# Schematic.net
KiCad netlist of a schematic drawn in EAGLE
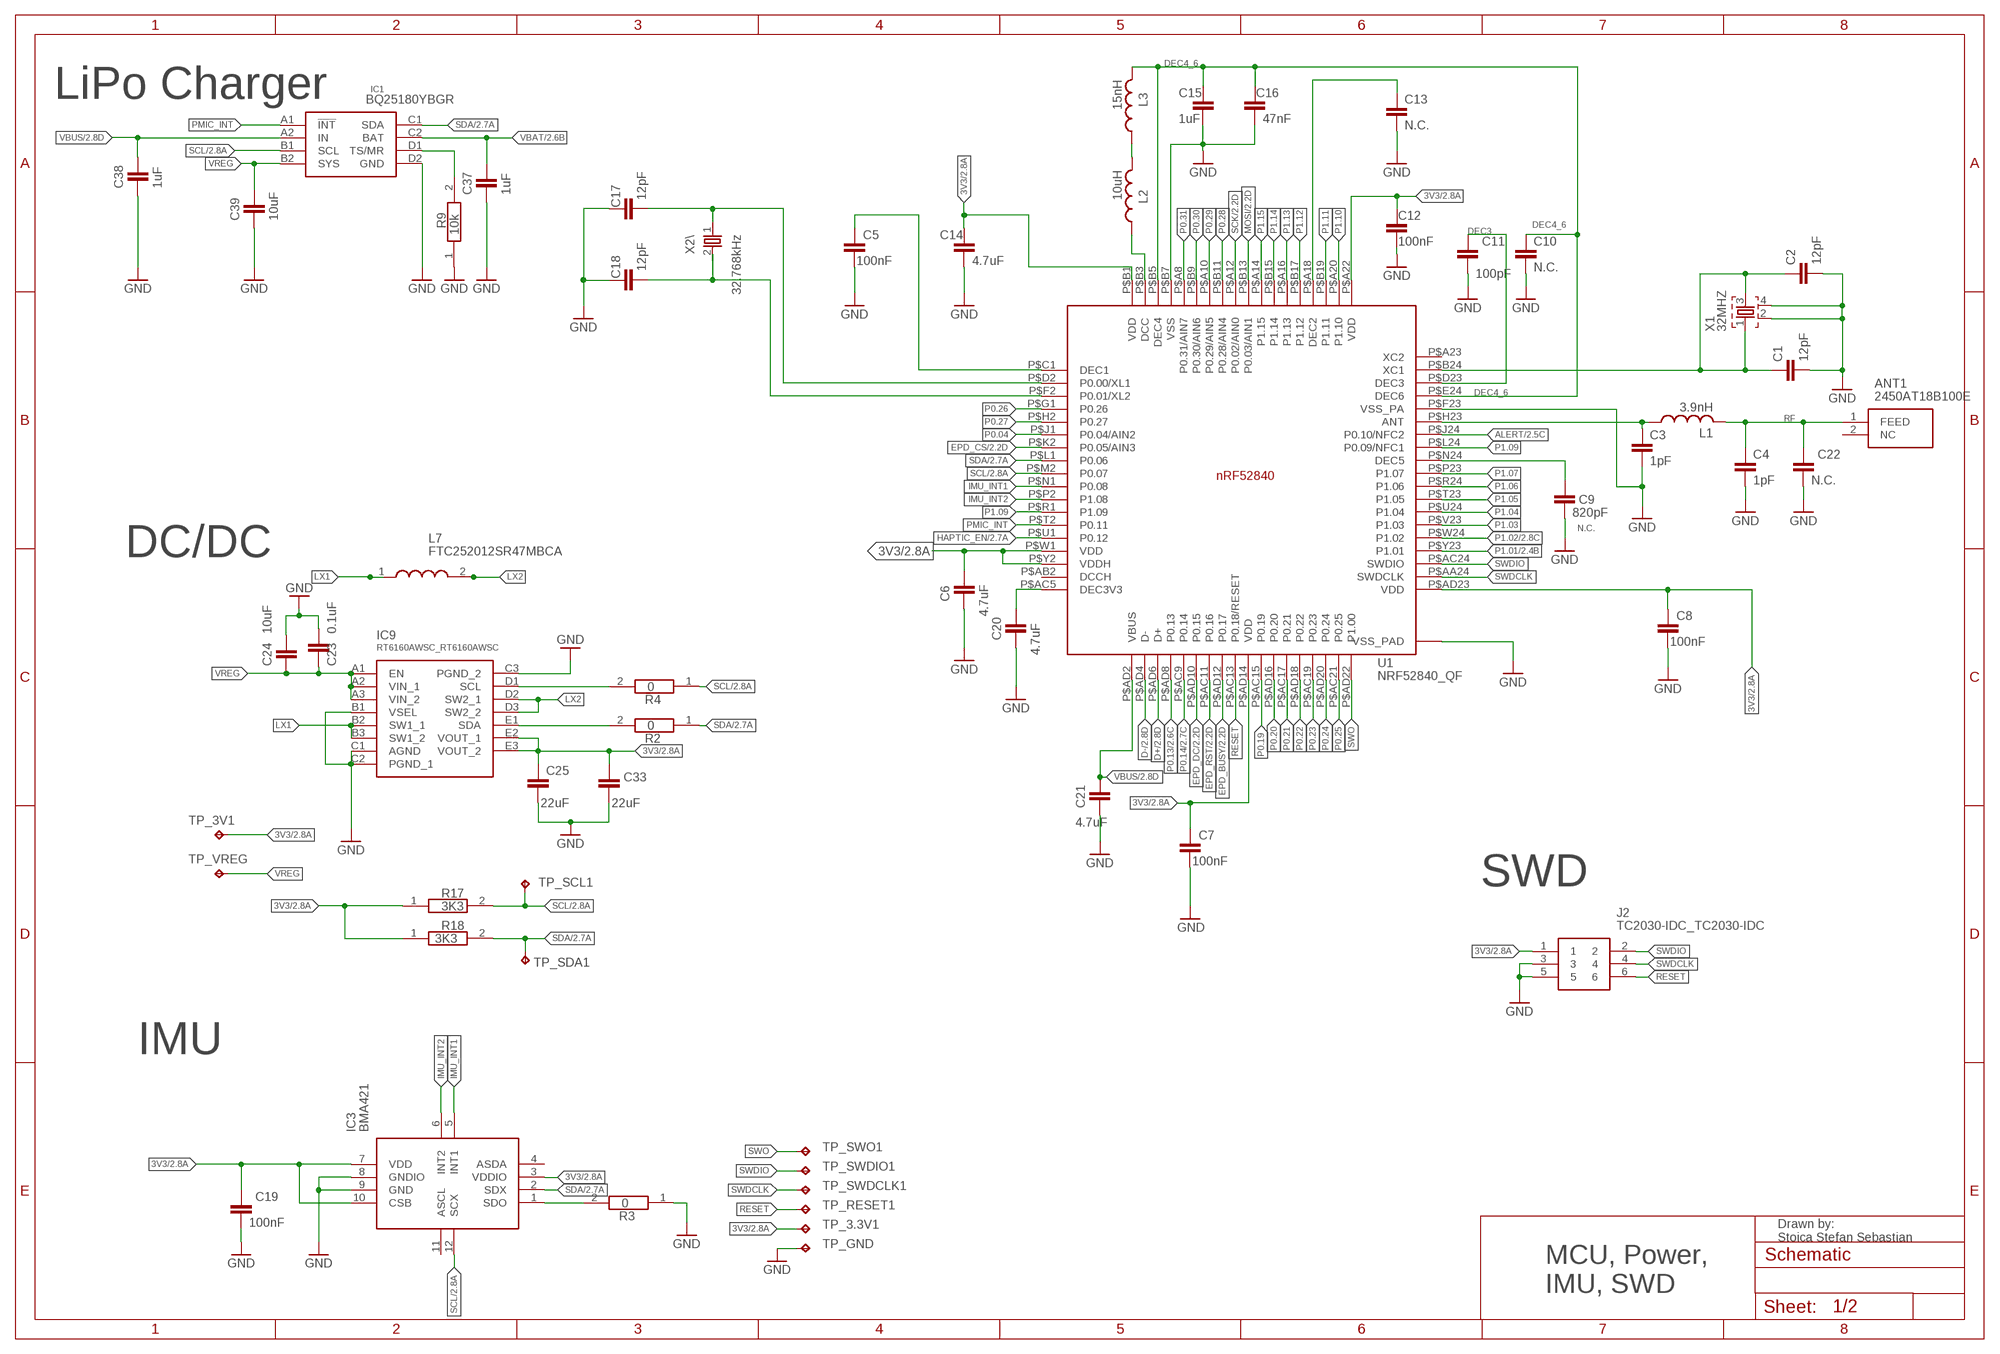
[diagram p0: schematic, sheet 1]
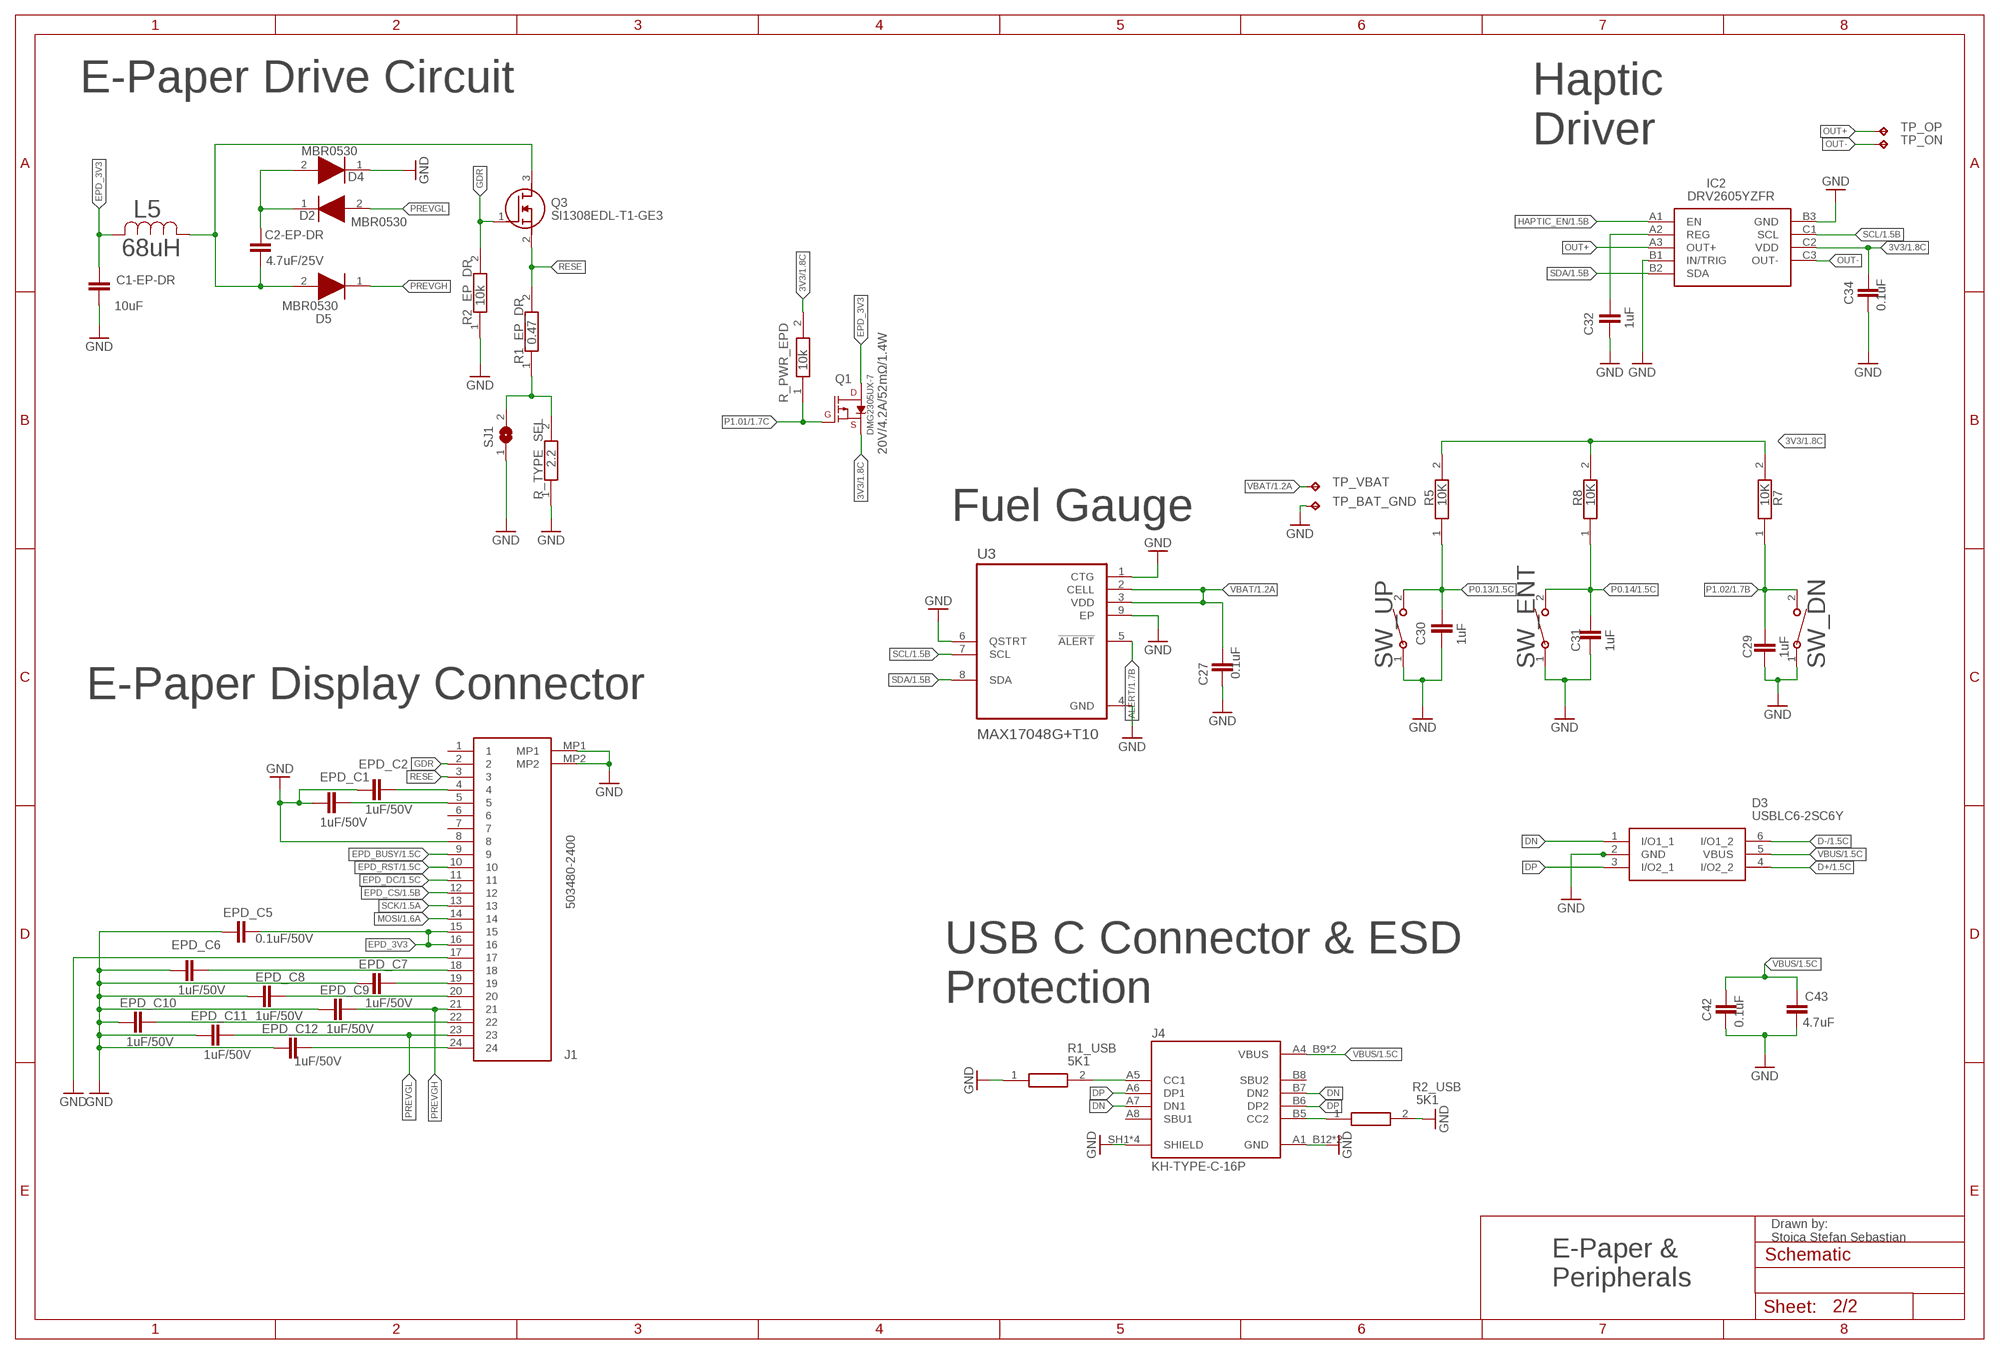
[diagram p1: schematic, sheet 2]

(export (version "E")
  (design (tool "Eeschema 10.0.6"))
  (components
    (comp (ref "C1-EP-DR")
      (value "10uF")
      (footprint "eagle-import:NORDIC_NRF_3_RESC0402_N")
      (libsource (lib "eagle-import") (part "NORDIC_NRF_3_CAPACITOR_0402_N"))
    )
    (comp (ref "C2-EP-DR")
      (value "4.7uF/25V")
      (footprint "eagle-import:NORDIC_NRF_3_RESC0603_N")
      (libsource (lib "eagle-import") (part "NORDIC_NRF_3_CAPACITOR_0603_N"))
    )
    (comp (ref "C27")
      (value "0.1uF")
      (footprint "eagle-import:NORDIC_NRF_3_RESC0201_N")
      (libsource (lib "eagle-import") (part "NORDIC_NRF_3_CAPACITOR_0201_N"))
    )
    (comp (ref "C29")
      (value "1uF")
      (footprint "eagle-import:NORDIC_NRF_3_RESC0402_N")
      (libsource (lib "eagle-import") (part "NORDIC_NRF_3_CAPACITOR_0402_N"))
    )
    (comp (ref "C30")
      (value "1uF")
      (footprint "eagle-import:NORDIC_NRF_3_RESC0402_N")
      (libsource (lib "eagle-import") (part "NORDIC_NRF_3_CAPACITOR_0402_N"))
    )
    (comp (ref "C31")
      (value "1uF")
      (footprint "eagle-import:NORDIC_NRF_3_RESC0402_N")
      (libsource (lib "eagle-import") (part "NORDIC_NRF_3_CAPACITOR_0402_N"))
    )
    (comp (ref "C32")
      (value "1uF")
      (footprint "eagle-import:NORDIC_NRF_3_RESC0402_N")
      (libsource (lib "eagle-import") (part "NORDIC_NRF_3_CAPACITOR_0402_N"))
    )
    (comp (ref "C34")
      (value "0.1uF")
      (footprint "eagle-import:NORDIC_NRF_3_RESC0201_N")
      (libsource (lib "eagle-import") (part "NORDIC_NRF_3_CAPACITOR_0201_N"))
    )
    (comp (ref "C42")
      (value "0.1uF")
      (footprint "eagle-import:NORDIC_NRF_3_RESC0201_N")
      (libsource (lib "eagle-import") (part "NORDIC_NRF_3_CAPACITOR_0201_N"))
    )
    (comp (ref "C43")
      (value "4.7uF")
      (footprint "eagle-import:NORDIC_NRF_3_RESC0402_N")
      (libsource (lib "eagle-import") (part "NORDIC_NRF_3_CAPACITOR_0402_N"))
    )
    (comp (ref "D2")
      (value "MBR0530")
      (footprint "eagle-import:ESP32_C6_LIBRARY_5_SOD3716X135N")
      (fields (field (name "MF") "ON Semiconductor"))
      (libsource (lib "eagle-import") (part "ESP32_C6_LIBRARY_5_MBR0530"))
    )
    (comp (ref "D3")
      (value "USBLC6-2SC6Y")
      (footprint "eagle-import:ESP32_C6_LIBRARY_3_SOT95P280X145-6N")
      (fields (field (name "MF") "STMicroelectronics"))
      (libsource (lib "eagle-import") (part "ESP32_C6_LIBRARY_3_USBLC6-2SC6Y"))
    )
    (comp (ref "D4")
      (value "MBR0530")
      (footprint "eagle-import:ESP32_C6_LIBRARY_5_SOD3716X135N")
      (fields (field (name "MF") "ON Semiconductor"))
      (libsource (lib "eagle-import") (part "ESP32_C6_LIBRARY_5_MBR0530"))
    )
    (comp (ref "D5")
      (value "MBR0530")
      (footprint "eagle-import:ESP32_C6_LIBRARY_5_SOD3716X135N")
      (fields (field (name "MF") "ON Semiconductor"))
      (libsource (lib "eagle-import") (part "ESP32_C6_LIBRARY_5_MBR0530"))
    )
    (comp (ref "EPD_C1")
      (value "1uF/50V")
      (footprint "eagle-import:NORDIC_NRF_3_RESC0402_N")
      (libsource (lib "eagle-import") (part "NORDIC_NRF_3_CAPACITOR_0402_N"))
    )
    (comp (ref "EPD_C2")
      (value "1uF/50V")
      (footprint "eagle-import:NORDIC_NRF_3_RESC0402_N")
      (libsource (lib "eagle-import") (part "NORDIC_NRF_3_CAPACITOR_0402_N"))
    )
    (comp (ref "EPD_C5")
      (value "0.1uF/50V")
      (footprint "eagle-import:NORDIC_NRF_3_RESC0402_N")
      (libsource (lib "eagle-import") (part "NORDIC_NRF_3_CAPACITOR_0402_N"))
    )
    (comp (ref "EPD_C6")
      (value "1uF/50V")
      (footprint "eagle-import:NORDIC_NRF_3_RESC0402_N")
      (libsource (lib "eagle-import") (part "NORDIC_NRF_3_CAPACITOR_0402_N"))
    )
    (comp (ref "EPD_C7")
      (value "1uF/50V")
      (footprint "eagle-import:NORDIC_NRF_3_RESC0402_N")
      (libsource (lib "eagle-import") (part "NORDIC_NRF_3_CAPACITOR_0402_N"))
    )
    (comp (ref "EPD_C8")
      (value "1uF/50V")
      (footprint "eagle-import:NORDIC_NRF_3_RESC0402_N")
      (libsource (lib "eagle-import") (part "NORDIC_NRF_3_CAPACITOR_0402_N"))
    )
    (comp (ref "EPD_C9")
      (value "1uF/50V")
      (footprint "eagle-import:NORDIC_NRF_3_RESC0402_N")
      (libsource (lib "eagle-import") (part "NORDIC_NRF_3_CAPACITOR_0402_N"))
    )
    (comp (ref "EPD_C10")
      (value "1uF/50V")
      (footprint "eagle-import:NORDIC_NRF_3_RESC0402_N")
      (libsource (lib "eagle-import") (part "NORDIC_NRF_3_CAPACITOR_0402_N"))
    )
    (comp (ref "EPD_C11")
      (value "1uF/50V")
      (footprint "eagle-import:NORDIC_NRF_3_RESC0402_N")
      (libsource (lib "eagle-import") (part "NORDIC_NRF_3_CAPACITOR_0402_N"))
    )
    (comp (ref "EPD_C12")
      (value "1uF/50V")
      (footprint "eagle-import:NORDIC_NRF_3_RESC0402_N")
      (libsource (lib "eagle-import") (part "NORDIC_NRF_3_CAPACITOR_0402_N"))
    )
    (comp (ref "IC2")
      (value "DRV2605YZFR")
      (footprint "eagle-import:DRV2605YZFR_BGA9C50P3X3_144X144X62")
      (libsource (lib "eagle-import") (part "DRV2605YZFR_DRV2605YZFR"))
    )
    (comp (ref "J1")
      (value "503480-2400")
      (footprint "eagle-import:503480-2400_5034802400")
      (fields (field (name "MOUSER_PART_NUMBER") "538-503480-2400"))
      (libsource (lib "eagle-import") (part "503480-2400_503480-2400"))
    )
    (comp (ref "J4")
      (value "KH-TYPE-C-16P")
      (footprint "eagle-import:KH-TYPE-C-16P_KINGHELM_KH-TYPE-C-16P")
      (fields (field (name "MF") "kinghelm"))
      (libsource (lib "eagle-import") (part "KH-TYPE-C-16P_KH-TYPE-C-16P"))
    )
    (comp (ref "L5")
      (value "68uH")
      (footprint "eagle-import:ESP32_C6_LIBRARY_2_IND_4828-WE-TPC_WRE")
      (fields
        (field (name "MANUFACTURER_PART_NUMBER") "744043680")
        (field (name "COPYRIGHT") "Copyright (C) 2024 Ultra Librarian. All rights reserved.")
      )
      (libsource (lib "eagle-import") (part "ESP32_C6_LIBRARY_2_744043680IND_4828-WE-TPC_WRE"))
    )
    (comp (ref "Q1")
      (value "20V/4.2A/52mΩ/1.4W")
      (footprint "eagle-import:ESP32_C6_LIBRARY_4_ESP32_C6_LIBRARY_4_ESP32_C6_LIBRARY_4_ESP32_C6_LIBRARY_4_ESP32_WROVER_SPARKFUN-DISCRETESEMI_SOT23-3")
      (libsource (lib "eagle-import") (part "ESP32_C6_LIBRARY_4_ESP32_WROVER_SPARKFUN-DISCRETESEMI_MOSFET_PCH-DMG2305UX-7"))
    )
    (comp (ref "Q3")
      (value "SI1308EDL-T1-GE3")
      (footprint "eagle-import:ESP32_C6_LIBRARY_6_SOT65P210X110-3N")
      (fields (field (name "MF") "Vishay Siliconix"))
      (libsource (lib "eagle-import") (part "ESP32_C6_LIBRARY_6_SI1308EDL-T1-GE3"))
    )
    (comp (ref "R1_EP_DR")
      (value "0.47")
      (footprint "eagle-import:CPF0201D7K68C1_0201")
      (libsource (lib "eagle-import") (part "CPF0201D7K68C1_CPF0201D7K68C1"))
    )
    (comp (ref "R1_USB")
      (value "5K1")
      (footprint "eagle-import:CPF0201D7K68C1_0201")
      (libsource (lib "eagle-import") (part "CPF0201D7K68C1_CPF0201D7K68C1"))
    )
    (comp (ref "R2_EP_DR")
      (value "10k")
      (footprint "eagle-import:CPF0201D7K68C1_0201")
      (libsource (lib "eagle-import") (part "CPF0201D7K68C1_CPF0201D7K68C1"))
    )
    (comp (ref "R2_USB")
      (value "5K1")
      (footprint "eagle-import:CPF0201D7K68C1_0201")
      (libsource (lib "eagle-import") (part "CPF0201D7K68C1_CPF0201D7K68C1"))
    )
    (comp (ref "R5")
      (value "10K")
      (footprint "eagle-import:CPF0201D7K68C1_0201")
      (libsource (lib "eagle-import") (part "CPF0201D7K68C1_CPF0201D7K68C1"))
    )
    (comp (ref "R7")
      (value "10K")
      (footprint "eagle-import:CPF0201D7K68C1_0201")
      (libsource (lib "eagle-import") (part "CPF0201D7K68C1_CPF0201D7K68C1"))
    )
    (comp (ref "R8")
      (value "10K")
      (footprint "eagle-import:CPF0201D7K68C1_0201")
      (libsource (lib "eagle-import") (part "CPF0201D7K68C1_CPF0201D7K68C1"))
    )
    (comp (ref "R_PWR_EPD")
      (value "10k")
      (footprint "eagle-import:CPF0201D7K68C1_0201")
      (libsource (lib "eagle-import") (part "CPF0201D7K68C1_CPF0201D7K68C1"))
    )
    (comp (ref "R_TYPE_SEL")
      (value "2.2")
      (footprint "eagle-import:CPF0201D7K68C1_0201")
      (libsource (lib "eagle-import") (part "CPF0201D7K68C1_CPF0201D7K68C1"))
    )
    (comp (ref "SJ1")
      (value "ESP32_C6_LIBRARY_7_JUMPER_SJ")
      (footprint "eagle-import:ESP32_C6_LIBRARY_7_JUMPER_SJ")
      (libsource (lib "eagle-import") (part "ESP32_C6_LIBRARY_7_JUMPER_SJ"))
    )
    (comp (ref "SW_DN")
      (value "2025-10-22_07-23-44_LIBRARY_EVP-AKE31ASW_EVP-AKE31A_PAN")
      (footprint "eagle-import:2025-10-22_07-23-44_LIBRARY_SW_EVP-AKE31A_PAN")
      (fields
        (field (name "MANUFACTURER_PART_NUMBER") "EVP-AKE31A")
        (field (name "COPYRIGHT") "Copyright (C) 2025 Ultra Librarian. All rights reserved.")
      )
      (libsource (lib "eagle-import") (part "2025-10-22_07-23-44_LIBRARY_EVP-AKE31ASW_EVP-AKE31A_PAN"))
    )
    (comp (ref "SW_ENT")
      (value "2025-10-22_07-23-44_LIBRARY_EVP-AKE31ASW_EVP-AKE31A_PAN")
      (footprint "eagle-import:2025-10-22_07-23-44_LIBRARY_SW_EVP-AKE31A_PAN")
      (fields
        (field (name "MANUFACTURER_PART_NUMBER") "EVP-AKE31A")
        (field (name "COPYRIGHT") "Copyright (C) 2025 Ultra Librarian. All rights reserved.")
      )
      (libsource (lib "eagle-import") (part "2025-10-22_07-23-44_LIBRARY_EVP-AKE31ASW_EVP-AKE31A_PAN"))
    )
    (comp (ref "SW_UP")
      (value "2025-10-22_07-23-44_LIBRARY_EVP-AKE31ASW_EVP-AKE31A_PAN")
      (footprint "eagle-import:2025-10-22_07-23-44_LIBRARY_SW_EVP-AKE31A_PAN")
      (fields
        (field (name "MANUFACTURER_PART_NUMBER") "EVP-AKE31A")
        (field (name "COPYRIGHT") "Copyright (C) 2025 Ultra Librarian. All rights reserved.")
      )
      (libsource (lib "eagle-import") (part "2025-10-22_07-23-44_LIBRARY_EVP-AKE31ASW_EVP-AKE31A_PAN"))
    )
    (comp (ref "TP_BAT_GND")
      (value "HECTOR_WATCH_1_TPTP20R")
      (footprint "eagle-import:HECTOR_WATCH_1_TP20R")
      (libsource (lib "eagle-import") (part "HECTOR_WATCH_1_TPTP20R"))
    )
    (comp (ref "TP_ON")
      (value "HECTOR_WATCH_1_TPTP20R")
      (footprint "eagle-import:HECTOR_WATCH_1_TP20R")
      (libsource (lib "eagle-import") (part "HECTOR_WATCH_1_TPTP20R"))
    )
    (comp (ref "TP_OP")
      (value "HECTOR_WATCH_1_TPTP20R")
      (footprint "eagle-import:HECTOR_WATCH_1_TP20R")
      (libsource (lib "eagle-import") (part "HECTOR_WATCH_1_TPTP20R"))
    )
    (comp (ref "TP_VBAT")
      (value "HECTOR_WATCH_1_TPTP20R")
      (footprint "eagle-import:HECTOR_WATCH_1_TP20R")
      (libsource (lib "eagle-import") (part "HECTOR_WATCH_1_TPTP20R"))
    )
    (comp (ref "U3")
      (value "MAX17048G+T10")
      (footprint "eagle-import:ESP32_C6_LIBRARY_SON50P200X200X80-9N")
      (fields (field (name "MF") "Analog Devices"))
      (libsource (lib "eagle-import") (part "ESP32_C6_LIBRARY_MAX17048G+T10"))
    )
    (comp (ref "ANT1")
      (value "2450AT18B100E")
      (footprint "eagle-import:2450AT18B100E_ANTC3216X140N")
      (fields (field (name "MOUSER_PART_NUMBER") "609-2450AT18B100E"))
      (libsource (lib "eagle-import") (part "2450AT18B100E_2450AT18B100E"))
    )
    (comp (ref "C1")
      (value "12pF")
      (footprint "eagle-import:NORDIC_NRF_3_RESC0201_N")
      (libsource (lib "eagle-import") (part "NORDIC_NRF_3_CAPACITOR_0201_N"))
    )
    (comp (ref "C2")
      (value "12pF")
      (footprint "eagle-import:NORDIC_NRF_3_RESC0201_N")
      (libsource (lib "eagle-import") (part "NORDIC_NRF_3_CAPACITOR_0201_N"))
    )
    (comp (ref "C3")
      (value "1pF")
      (footprint "eagle-import:NORDIC_NRF_3_RESC0201_N")
      (libsource (lib "eagle-import") (part "NORDIC_NRF_3_CAPACITOR_0201_N"))
    )
    (comp (ref "C4")
      (value "1pF")
      (footprint "eagle-import:NORDIC_NRF_3_RESC0201_N")
      (libsource (lib "eagle-import") (part "NORDIC_NRF_3_CAPACITOR_0201_N"))
    )
    (comp (ref "C5")
      (value "100nF")
      (footprint "eagle-import:NORDIC_NRF_3_RESC0201_N")
      (libsource (lib "eagle-import") (part "NORDIC_NRF_3_CAPACITOR_0201_N"))
    )
    (comp (ref "C6")
      (value "4.7uF")
      (footprint "eagle-import:NORDIC_NRF_3_RESC0402_N")
      (libsource (lib "eagle-import") (part "NORDIC_NRF_3_CAPACITOR_0402_N"))
    )
    (comp (ref "C7")
      (value "100nF")
      (footprint "eagle-import:NORDIC_NRF_3_RESC0201_N")
      (libsource (lib "eagle-import") (part "NORDIC_NRF_3_CAPACITOR_0201_N"))
    )
    (comp (ref "C8")
      (value "100nF")
      (footprint "eagle-import:NORDIC_NRF_3_RESC0201_N")
      (libsource (lib "eagle-import") (part "NORDIC_NRF_3_CAPACITOR_0201_N"))
    )
    (comp (ref "C9")
      (value "820pF")
      (footprint "eagle-import:NORDIC_NRF_3_RESC0201_N")
      (libsource (lib "eagle-import") (part "NORDIC_NRF_3_CAPACITOR_0201_N"))
    )
    (comp (ref "C10")
      (value "N.C.")
      (footprint "eagle-import:NORDIC_NRF_3_RESC0201_N")
      (libsource (lib "eagle-import") (part "NORDIC_NRF_3_CAPACITOR_0201_N"))
    )
    (comp (ref "C11")
      (value "100pF")
      (footprint "eagle-import:NORDIC_NRF_3_RESC0201_N")
      (libsource (lib "eagle-import") (part "NORDIC_NRF_3_CAPACITOR_0201_N"))
    )
    (comp (ref "C12")
      (value "100nF")
      (footprint "eagle-import:NORDIC_NRF_3_RESC0201_N")
      (libsource (lib "eagle-import") (part "NORDIC_NRF_3_CAPACITOR_0201_N"))
    )
    (comp (ref "C13")
      (value "N.C.")
      (footprint "eagle-import:NORDIC_NRF_3_RESC0201_N")
      (libsource (lib "eagle-import") (part "NORDIC_NRF_3_CAPACITOR_0201_N"))
    )
    (comp (ref "C14")
      (value "4.7uF")
      (footprint "eagle-import:NORDIC_NRF_3_RESC0402_N")
      (libsource (lib "eagle-import") (part "NORDIC_NRF_3_CAPACITOR_0402_N"))
    )
    (comp (ref "C15")
      (value "1uF")
      (footprint "eagle-import:NORDIC_NRF_3_RESC0402_N")
      (libsource (lib "eagle-import") (part "NORDIC_NRF_3_CAPACITOR_0402_N"))
    )
    (comp (ref "C16")
      (value "47nF")
      (footprint "eagle-import:NORDIC_NRF_3_RESC0201_N")
      (libsource (lib "eagle-import") (part "NORDIC_NRF_3_CAPACITOR_0201_N"))
    )
    (comp (ref "C17")
      (value "12pF")
      (footprint "eagle-import:NORDIC_NRF_3_RESC0201_N")
      (libsource (lib "eagle-import") (part "NORDIC_NRF_3_CAPACITOR_0201_N"))
    )
    (comp (ref "C18")
      (value "12pF")
      (footprint "eagle-import:NORDIC_NRF_3_RESC0201_N")
      (libsource (lib "eagle-import") (part "NORDIC_NRF_3_CAPACITOR_0201_N"))
    )
    (comp (ref "C19")
      (value "100nF")
      (footprint "eagle-import:NORDIC_NRF_3_RESC0201_N")
      (libsource (lib "eagle-import") (part "NORDIC_NRF_3_CAPACITOR_0201_N"))
    )
    (comp (ref "C20")
      (value "4.7uF")
      (footprint "eagle-import:NORDIC_NRF_3_RESC0402_N")
      (libsource (lib "eagle-import") (part "NORDIC_NRF_3_CAPACITOR_0402_N"))
    )
    (comp (ref "C21")
      (value "4.7uF")
      (footprint "eagle-import:NORDIC_NRF_3_RESC0402_N")
      (libsource (lib "eagle-import") (part "NORDIC_NRF_3_CAPACITOR_0402_N"))
    )
    (comp (ref "C22")
      (value "N.C.")
      (footprint "eagle-import:NORDIC_NRF_3_RESC0201_N")
      (libsource (lib "eagle-import") (part "NORDIC_NRF_3_CAPACITOR_0201_N"))
    )
    (comp (ref "C23")
      (value "0.1uF")
      (footprint "eagle-import:NORDIC_NRF_3_RESC0201_N")
      (libsource (lib "eagle-import") (part "NORDIC_NRF_3_CAPACITOR_0201_N"))
    )
    (comp (ref "C24")
      (value "10uF")
      (footprint "eagle-import:NORDIC_NRF_3_RESC0402_N")
      (libsource (lib "eagle-import") (part "NORDIC_NRF_3_CAPACITOR_0402_N"))
    )
    (comp (ref "C25")
      (value "22uF")
      (footprint "eagle-import:NORDIC_NRF_3_RESC0603_N")
      (libsource (lib "eagle-import") (part "InkTime_v5_vf.birtyhFxSUisHCd2wUyXPg_NORDIC_NRF_3_CAPACITOR_0603_N"))
    )
    (comp (ref "C33")
      (value "22uF")
      (footprint "eagle-import:NORDIC_NRF_3_RESC0603_N")
      (libsource (lib "eagle-import") (part "InkTime_v5_vf.birtyhFxSUisHCd2wUyXPg_NORDIC_NRF_3_CAPACITOR_0603_N"))
    )
    (comp (ref "C37")
      (value "1uF")
      (footprint "eagle-import:NORDIC_NRF_3_RESC0402_N")
      (libsource (lib "eagle-import") (part "NORDIC_NRF_3_CAPACITOR_0402_N"))
    )
    (comp (ref "C38")
      (value "1uF")
      (footprint "eagle-import:NORDIC_NRF_3_RESC0402_N")
      (libsource (lib "eagle-import") (part "NORDIC_NRF_3_CAPACITOR_0402_N"))
    )
    (comp (ref "C39")
      (value "10uF")
      (footprint "eagle-import:NORDIC_NRF_3_RESC0603_N")
      (libsource (lib "eagle-import") (part "InkTime_v5_vf.birtyhFxSUisHCd2wUyXPg_NORDIC_NRF_3_CAPACITOR_0603_N"))
    )
    (comp (ref "IC1")
      (value "BQ25180YBGR")
      (footprint "eagle-import:BQ25180YBGR_BGA8C40P2X4_100X155X50")
      (fields (field (name "MOUSER_PART_NUMBER") "595-BQ25180YBGR"))
      (libsource (lib "eagle-import") (part "BQ25180YBGR_BQ25180YBGR"))
    )
    (comp (ref "IC3")
      (value "BMA421")
      (footprint "eagle-import:BMA423_BMA423")
      (fields
        (field (name "ARROW_PART_NUMBER") "BMA423")
        (field (name "MOUSER_PART_NUMBER") "262-BMA423")
        (field (name "ARROW_PART_NUMBER_1") "BMA421")
        (field (name "MANUFACTURER_PART_NUMBER") "BMA421")
        (field (name "MOUSER_PART_NUMBER_1") "262-BMA421")
      )
      (libsource (lib "eagle-import") (part "BMA423_BMA423"))
    )
    (comp (ref "IC9")
      (value "RT6160AWSC_RT6160AWSC")
      (footprint "eagle-import:RT6160AWSC_BGA15C40P3X5_140X230X60")
      (fields
        (field (name "MANUFACTURER_PART_NUMBER") "RT6160AWSC")
        (field (name "MOUSER_PART_NUMBER") "835-RT6160AWSC")
      )
      (libsource (lib "eagle-import") (part "RT6160AWSC_RT6160AWSC"))
    )
    (comp (ref "J2")
      (value "TC2030-IDC_TC2030-IDC")
      (footprint "eagle-import:TC2030-IDC_TC2030IDC")
      (fields (field (name "MANUFACTURER_PART_NUMBER") "TC2030-IDC"))
      (libsource (lib "eagle-import") (part "TC2030-IDC_TC2030-IDC"))
    )
    (comp (ref "L1")
      (value "3.9nH")
      (footprint "eagle-import:NORDIC_NRF_2_RESC0402_L")
      (libsource (lib "eagle-import") (part "NORDIC_NRF_2_INDUCTOR_0402_L"))
    )
    (comp (ref "L2")
      (value "10uH")
      (footprint "eagle-import:NORDIC_NRF_2_RESC0603_N")
      (libsource (lib "eagle-import") (part "InkTime_v5_vf.birtyhFxSUisHCd2wUyXPg_NORDIC_NRF_2_INDUCTOR_0603_N"))
    )
    (comp (ref "L3")
      (value "15nH")
      (footprint "eagle-import:NORDIC_NRF_2_RESC0402_L")
      (libsource (lib "eagle-import") (part "NORDIC_NRF_2_INDUCTOR_0402_L"))
    )
    (comp (ref "L7")
      (value "FTC252012SR47MBCA")
      (footprint "eagle-import:MLP2016SR47MT0S1_INDC2016X100N")
      (libsource (lib "eagle-import") (part "MLP2016SR47MT0S1_FTC252012SR47MBCA"))
    )
    (comp (ref "R2")
      (value "0")
      (footprint "eagle-import:CPF0201D7K68C1_0201")
      (libsource (lib "eagle-import") (part "CPF0201D7K68C1_CPF0201D7K68C1"))
    )
    (comp (ref "R3")
      (value "0")
      (footprint "eagle-import:CPF0201D7K68C1_0201")
      (libsource (lib "eagle-import") (part "CPF0201D7K68C1_CPF0201D7K68C1"))
    )
    (comp (ref "R4")
      (value "0")
      (footprint "eagle-import:CPF0201D7K68C1_0201")
      (libsource (lib "eagle-import") (part "CPF0201D7K68C1_CPF0201D7K68C1"))
    )
    (comp (ref "R9")
      (value "10k")
      (footprint "eagle-import:CPF0201D7K68C1_0201")
      (libsource (lib "eagle-import") (part "CPF0201D7K68C1_CPF0201D7K68C1"))
    )
    (comp (ref "R17")
      (value "3K3")
      (footprint "eagle-import:CPF0201D7K68C1_0201")
      (libsource (lib "eagle-import") (part "CPF0201D7K68C1_CPF0201D7K68C1"))
    )
    (comp (ref "R18")
      (value "3K3")
      (footprint "eagle-import:CPF0201D7K68C1_0201")
      (libsource (lib "eagle-import") (part "CPF0201D7K68C1_CPF0201D7K68C1"))
    )
    (comp (ref "TP_3.3V1")
      (value "HECTOR_WATCH_1_TPTP20R")
      (footprint "eagle-import:HECTOR_WATCH_1_TP20R")
      (libsource (lib "eagle-import") (part "HECTOR_WATCH_1_TPTP20R"))
    )
    (comp (ref "TP_3V1")
      (value "HECTOR_WATCH_1_TPTP20R")
      (footprint "eagle-import:HECTOR_WATCH_1_TP20R")
      (libsource (lib "eagle-import") (part "HECTOR_WATCH_1_TPTP20R"))
    )
    (comp (ref "TP_GND")
      (value "HECTOR_WATCH_1_TPTP20R")
      (footprint "eagle-import:HECTOR_WATCH_1_TP20R")
      (libsource (lib "eagle-import") (part "HECTOR_WATCH_1_TPTP20R"))
    )
    (comp (ref "TP_RESET1")
      (value "HECTOR_WATCH_1_TPTP20R")
      (footprint "eagle-import:HECTOR_WATCH_1_TP20R")
      (libsource (lib "eagle-import") (part "HECTOR_WATCH_1_TPTP20R"))
    )
    (comp (ref "TP_SCL1")
      (value "HECTOR_WATCH_1_TPTP20R")
      (footprint "eagle-import:HECTOR_WATCH_1_TP20R")
      (libsource (lib "eagle-import") (part "HECTOR_WATCH_1_TPTP20R"))
    )
    (comp (ref "TP_SDA1")
      (value "HECTOR_WATCH_1_TPTP20R")
      (footprint "eagle-import:HECTOR_WATCH_1_TP20R")
      (libsource (lib "eagle-import") (part "HECTOR_WATCH_1_TPTP20R"))
    )
    (comp (ref "TP_SWDCLK1")
      (value "HECTOR_WATCH_1_TPTP20R")
      (footprint "eagle-import:HECTOR_WATCH_1_TP20R")
      (libsource (lib "eagle-import") (part "HECTOR_WATCH_1_TPTP20R"))
    )
    (comp (ref "TP_SWDIO1")
      (value "HECTOR_WATCH_1_TPTP20R")
      (footprint "eagle-import:HECTOR_WATCH_1_TP20R")
      (libsource (lib "eagle-import") (part "HECTOR_WATCH_1_TPTP20R"))
    )
    (comp (ref "TP_SWO1")
      (value "HECTOR_WATCH_1_TPTP20R")
      (footprint "eagle-import:HECTOR_WATCH_1_TP20R")
      (libsource (lib "eagle-import") (part "HECTOR_WATCH_1_TPTP20R"))
    )
    (comp (ref "TP_VREG")
      (value "HECTOR_WATCH_1_TPTP20R")
      (footprint "eagle-import:HECTOR_WATCH_1_TP20R")
      (libsource (lib "eagle-import") (part "HECTOR_WATCH_1_TPTP20R"))
    )
    (comp (ref "U1")
      (value "NRF52840_QF")
      (footprint "eagle-import:NORDIC_NRF_4_AQFN50P700X700X85_HS-74N")
      (libsource (lib "eagle-import") (part "NORDIC_NRF_4_NRF52840_QF"))
    )
    (comp (ref "X1")
      (value "32MHZ")
      (footprint "eagle-import:NORDIC_NRF_BT-XTAL_2016_N")
      (libsource (lib "eagle-import") (part "NORDIC_NRF_XTAL_32MHZ"))
    )
    (comp (ref "X2\\")
      (value "32.768kHz")
      (footprint "eagle-import:NORDIC_NRF_1_XTAL_3215_N")
      (libsource (lib "eagle-import") (part "NORDIC_NRF_1_XTAL_32KHZ"))
    )
  )
  (nets
    (net (code "1") (name "3V3") (class "Default")
      (node (ref "C12") (pin "2") (pinfunction "2_2") (pintype "passive"))
      (node (ref "C14") (pin "1") (pinfunction "1_1") (pintype "passive"))
      (node (ref "C19") (pin "2") (pinfunction "2_2") (pintype "passive"))
      (node (ref "C25") (pin "1") (pinfunction "1_1") (pintype "passive"))
      (node (ref "C33") (pin "1") (pinfunction "1_1") (pintype "passive"))
      (node (ref "C34") (pin "1") (pinfunction "1_1") (pintype "passive"))
      (node (ref "C6") (pin "1") (pinfunction "1_1") (pintype "passive"))
      (node (ref "C7") (pin "1") (pinfunction "1_1") (pintype "passive"))
      (node (ref "C8") (pin "1") (pinfunction "1_1") (pintype "passive"))
      (node (ref "IC2") (pin "C2") (pinfunction "VDD_C2") (pintype "bidirectional"))
      (node (ref "IC3") (pin "10") (pinfunction "CSB_10") (pintype "bidirectional"))
      (node (ref "IC3") (pin "3") (pinfunction "VDDIO_3") (pintype "bidirectional"))
      (node (ref "IC3") (pin "7") (pinfunction "VDD_7") (pintype "bidirectional"))
      (node (ref "IC9") (pin "E2") (pinfunction "VOUT_1_E2") (pintype "bidirectional"))
      (node (ref "IC9") (pin "E3") (pinfunction "VOUT_2_E3") (pintype "bidirectional"))
      (node (ref "J2") (pin "1") (pinfunction "1_1") (pintype "bidirectional"))
      (node (ref "Q1") (pin "2") (pinfunction "S_2") (pintype "bidirectional"))
      (node (ref "R17") (pin "1") (pinfunction "1_1") (pintype "bidirectional"))
      (node (ref "R18") (pin "1") (pinfunction "1_1") (pintype "bidirectional"))
      (node (ref "R5") (pin "2") (pinfunction "2_2") (pintype "bidirectional"))
      (node (ref "R7") (pin "2") (pinfunction "2_2") (pintype "bidirectional"))
      (node (ref "R8") (pin "2") (pinfunction "2_2") (pintype "bidirectional"))
      (node (ref "R_PWR_EPD") (pin "2") (pinfunction "2_2") (pintype "bidirectional"))
      (node (ref "TP_3.3V1") (pin "TP") (pinfunction "TP_TP") (pintype "input"))
      (node (ref "TP_3V1") (pin "TP") (pinfunction "TP_TP") (pintype "input"))
      (node (ref "U1") (pin "P$A22") (pinfunction "VDD_P$A22") (pintype "power_in"))
      (node (ref "U1") (pin "P$AD14") (pinfunction "VDD_P$AD14") (pintype "power_in"))
      (node (ref "U1") (pin "P$AD23") (pinfunction "VDD_P$AD23") (pintype "power_in"))
      (node (ref "U1") (pin "P$B1") (pinfunction "VDD_P$B1") (pintype "power_in"))
      (node (ref "U1") (pin "P$W1") (pinfunction "VDD_P$W1") (pintype "power_in"))
      (node (ref "U1") (pin "P$Y2") (pinfunction "VDDH_P$Y2") (pintype "power_in"))
    )
    (net (code "2") (name "ALERT") (class "Default")
      (node (ref "U1") (pin "P$J24") (pinfunction "P0.10/NFC2_P$J24") (pintype "bidirectional"))
      (node (ref "U3") (pin "5") (pinfunction "~{ALERT}_5") (pintype "output"))
    )
    (net (code "3") (name "D+") (class "Default")
      (node (ref "D3") (pin "4") (pinfunction "I/O2_2_4") (pintype "bidirectional"))
      (node (ref "U1") (pin "P$AD6") (pinfunction "D+_P$AD6") (pintype "bidirectional"))
    )
    (net (code "4") (name "D-") (class "Default")
      (node (ref "D3") (pin "6") (pinfunction "I/O1_2_6") (pintype "bidirectional"))
      (node (ref "U1") (pin "P$AD4") (pinfunction "D-_P$AD4") (pintype "bidirectional"))
    )
    (net (code "5") (name "DN") (class "Default")
      (node (ref "D3") (pin "1") (pinfunction "I/O1_1_1") (pintype "bidirectional"))
      (node (ref "J4") (pin "A7") (pinfunction "DN1_A7") (pintype "bidirectional"))
      (node (ref "J4") (pin "B7") (pinfunction "DN2_B7") (pintype "bidirectional"))
    )
    (net (code "6") (name "DP") (class "Default")
      (node (ref "D3") (pin "3") (pinfunction "I/O2_1_3") (pintype "bidirectional"))
      (node (ref "J4") (pin "A6") (pinfunction "DP1_A6") (pintype "bidirectional"))
      (node (ref "J4") (pin "B6") (pinfunction "DP2_B6") (pintype "bidirectional"))
    )
    (net (code "7") (name "EPD_3V3") (class "Default")
      (node (ref "C1-EP-DR") (pin "1") (pinfunction "1_1") (pintype "passive"))
      (node (ref "EPD_C5") (pin "2") (pinfunction "2_2") (pintype "passive"))
      (node (ref "J1") (pin "15") (pinfunction "15_15") (pintype "bidirectional"))
      (node (ref "J1") (pin "16") (pinfunction "16_16") (pintype "bidirectional"))
      (node (ref "L5") (pin "2") (pinfunction "2_2") (pintype "passive"))
      (node (ref "Q1") (pin "3") (pinfunction "D_3") (pintype "bidirectional"))
    )
    (net (code "8") (name "EPD_BUSY") (class "Default")
      (node (ref "J1") (pin "9") (pinfunction "9_9") (pintype "bidirectional"))
      (node (ref "U1") (pin "P$AD12") (pinfunction "P0.17_P$AD12") (pintype "bidirectional"))
    )
    (net (code "9") (name "EPD_CS") (class "Default")
      (node (ref "J1") (pin "12") (pinfunction "12_12") (pintype "bidirectional"))
      (node (ref "U1") (pin "P$K2") (pinfunction "P0.05/AIN3_P$K2") (pintype "bidirectional"))
    )
    (net (code "10") (name "EPD_DC") (class "Default")
      (node (ref "J1") (pin "11") (pinfunction "11_11") (pintype "bidirectional"))
      (node (ref "U1") (pin "P$AD10") (pinfunction "P0.15_P$AD10") (pintype "bidirectional"))
    )
    (net (code "11") (name "EPD_RST") (class "Default")
      (node (ref "J1") (pin "10") (pinfunction "10_10") (pintype "bidirectional"))
      (node (ref "U1") (pin "P$AC11") (pinfunction "P0.16_P$AC11") (pintype "bidirectional"))
    )
    (net (code "12") (name "GDR") (class "Default")
      (node (ref "J1") (pin "2") (pinfunction "2_2") (pintype "bidirectional"))
      (node (ref "Q3") (pin "1") (pinfunction "G_1") (pintype "bidirectional"))
      (node (ref "R2_EP_DR") (pin "2") (pinfunction "2_2") (pintype "bidirectional"))
    )
    (net (code "13") (name "GND") (class "Default")
      (node (ref "C1") (pin "2") (pinfunction "2_2") (pintype "passive"))
      (node (ref "C1-EP-DR") (pin "2") (pinfunction "2_2") (pintype "passive"))
      (node (ref "C10") (pin "1") (pinfunction "1_1") (pintype "passive"))
      (node (ref "C11") (pin "1") (pinfunction "1_1") (pintype "passive"))
      (node (ref "C12") (pin "1") (pinfunction "1_1") (pintype "passive"))
      (node (ref "C13") (pin "1") (pinfunction "1_1") (pintype "passive"))
      (node (ref "C14") (pin "2") (pinfunction "2_2") (pintype "passive"))
      (node (ref "C15") (pin "2") (pinfunction "2_2") (pintype "passive"))
      (node (ref "C16") (pin "1") (pinfunction "1_1") (pintype "passive"))
      (node (ref "C17") (pin "1") (pinfunction "1_1") (pintype "passive"))
      (node (ref "C18") (pin "1") (pinfunction "1_1") (pintype "passive"))
      (node (ref "C19") (pin "1") (pinfunction "1_1") (pintype "passive"))
      (node (ref "C2") (pin "2") (pinfunction "2_2") (pintype "passive"))
      (node (ref "C20") (pin "2") (pinfunction "2_2") (pintype "passive"))
      (node (ref "C21") (pin "2") (pinfunction "2_2") (pintype "passive"))
      (node (ref "C22") (pin "1") (pinfunction "1_1") (pintype "passive"))
      (node (ref "C23") (pin "1") (pinfunction "1_1") (pintype "passive"))
      (node (ref "C24") (pin "1") (pinfunction "1_1") (pintype "passive"))
      (node (ref "C25") (pin "2") (pinfunction "2_2") (pintype "passive"))
      (node (ref "C27") (pin "1") (pinfunction "1_1") (pintype "passive"))
      (node (ref "C29") (pin "2") (pinfunction "2_2") (pintype "passive"))
      (node (ref "C3") (pin "1") (pinfunction "1_1") (pintype "passive"))
      (node (ref "C30") (pin "1") (pinfunction "1_1") (pintype "passive"))
      (node (ref "C31") (pin "1") (pinfunction "1_1") (pintype "passive"))
      (node (ref "C32") (pin "1") (pinfunction "1_1") (pintype "passive"))
      (node (ref "C33") (pin "2") (pinfunction "2_2") (pintype "passive"))
      (node (ref "C34") (pin "2") (pinfunction "2_2") (pintype "passive"))
      (node (ref "C37") (pin "2") (pinfunction "2_2") (pintype "passive"))
      (node (ref "C38") (pin "2") (pinfunction "2_2") (pintype "passive"))
      (node (ref "C39") (pin "2") (pinfunction "2_2") (pintype "passive"))
      (node (ref "C4") (pin "1") (pinfunction "1_1") (pintype "passive"))
      (node (ref "C42") (pin "2") (pinfunction "2_2") (pintype "passive"))
      (node (ref "C43") (pin "2") (pinfunction "2_2") (pintype "passive"))
      (node (ref "C5") (pin "2") (pinfunction "2_2") (pintype "passive"))
      (node (ref "C6") (pin "2") (pinfunction "2_2") (pintype "passive"))
      (node (ref "C7") (pin "2") (pinfunction "2_2") (pintype "passive"))
      (node (ref "C8") (pin "2") (pinfunction "2_2") (pintype "passive"))
      (node (ref "C9") (pin "1") (pinfunction "1_1") (pintype "passive"))
      (node (ref "D3") (pin "2") (pinfunction "GND_2") (pintype "bidirectional"))
      (node (ref "D4") (pin "1") (pinfunction "K_1") (pintype "bidirectional"))
      (node (ref "EPD_C1") (pin "1") (pinfunction "1_1") (pintype "passive"))
      (node (ref "EPD_C10") (pin "1") (pinfunction "1_1") (pintype "passive"))
      (node (ref "EPD_C11") (pin "1") (pinfunction "1_1") (pintype "passive"))
      (node (ref "EPD_C12") (pin "1") (pinfunction "1_1") (pintype "passive"))
      (node (ref "EPD_C2") (pin "1") (pinfunction "1_1") (pintype "passive"))
      (node (ref "EPD_C5") (pin "1") (pinfunction "1_1") (pintype "passive"))
      (node (ref "EPD_C6") (pin "1") (pinfunction "1_1") (pintype "passive"))
      (node (ref "EPD_C7") (pin "1") (pinfunction "1_1") (pintype "passive"))
      (node (ref "EPD_C8") (pin "1") (pinfunction "1_1") (pintype "passive"))
      (node (ref "EPD_C9") (pin "1") (pinfunction "1_1") (pintype "passive"))
      (node (ref "IC1") (pin "D2") (pinfunction "GND_D2") (pintype "bidirectional"))
      (node (ref "IC2") (pin "B1") (pinfunction "IN/TRIG_B1") (pintype "bidirectional"))
      (node (ref "IC2") (pin "B3") (pinfunction "GND_B3") (pintype "bidirectional"))
      (node (ref "IC3") (pin "8") (pinfunction "GNDIO_8") (pintype "bidirectional"))
      (node (ref "IC3") (pin "9") (pinfunction "GND_9") (pintype "bidirectional"))
      (node (ref "IC9") (pin "B1") (pinfunction "VSEL_B1") (pintype "bidirectional"))
      (node (ref "IC9") (pin "C1") (pinfunction "AGND_C1") (pintype "bidirectional"))
      (node (ref "IC9") (pin "C2") (pinfunction "PGND_1_C2") (pintype "bidirectional"))
      (node (ref "IC9") (pin "C3") (pinfunction "PGND_2_C3") (pintype "bidirectional"))
      (node (ref "J1") (pin "17") (pinfunction "17_17") (pintype "bidirectional"))
      (node (ref "J1") (pin "8") (pinfunction "8_8") (pintype "bidirectional"))
      (node (ref "J1") (pin "MP1") (pinfunction "MP1_MP1") (pintype "bidirectional"))
      (node (ref "J1") (pin "MP2") (pinfunction "MP2_MP2") (pintype "bidirectional"))
      (node (ref "J2") (pin "3") (pinfunction "3_3") (pintype "bidirectional"))
      (node (ref "J2") (pin "5") (pinfunction "5_5") (pintype "bidirectional"))
      (node (ref "J4") (pin "A12_B1") (pinfunction "GND_A12_B1") (pintype "power_in"))
      (node (ref "J4") (pin "A1_B12") (pinfunction "GND_A1_B12") (pintype "power_in"))
      (node (ref "J4") (pin "SH1") (pinfunction "SHIELD_SH1") (pintype "passive"))
      (node (ref "J4") (pin "SH2") (pinfunction "SHIELD_SH2") (pintype "passive"))
      (node (ref "J4") (pin "SH3") (pinfunction "SHIELD_SH3") (pintype "passive"))
      (node (ref "J4") (pin "SH4") (pinfunction "SHIELD_SH4") (pintype "passive"))
      (node (ref "R1_USB") (pin "1") (pinfunction "1_1") (pintype "bidirectional"))
      (node (ref "R2_EP_DR") (pin "1") (pinfunction "1_1") (pintype "bidirectional"))
      (node (ref "R2_USB") (pin "2") (pinfunction "2_2") (pintype "bidirectional"))
      (node (ref "R3") (pin "1") (pinfunction "1_1") (pintype "bidirectional"))
      (node (ref "R9") (pin "1") (pinfunction "1_1") (pintype "bidirectional"))
      (node (ref "R_TYPE_SEL") (pin "1") (pinfunction "1_1") (pintype "bidirectional"))
      (node (ref "SJ1") (pin "1") (pinfunction "1_1") (pintype "passive"))
      (node (ref "SW_DN") (pin "1") (pinfunction "1_1") (pintype "passive"))
      (node (ref "SW_ENT") (pin "1") (pinfunction "1_1") (pintype "passive"))
      (node (ref "SW_UP") (pin "1") (pinfunction "1_1") (pintype "passive"))
      (node (ref "TP_BAT_GND") (pin "TP") (pinfunction "TP_TP") (pintype "input"))
      (node (ref "TP_GND") (pin "TP") (pinfunction "TP_TP") (pintype "input"))
      (node (ref "U1") (pin "P$74") (pinfunction "VSS_PAD_P$74") (pintype "bidirectional"))
      (node (ref "U1") (pin "P$75") (pinfunction "VSS_PAD_P$75") (pintype "bidirectional"))
      (node (ref "U1") (pin "P$76") (pinfunction "VSS_PAD_P$76") (pintype "bidirectional"))
      (node (ref "U1") (pin "P$77") (pinfunction "VSS_PAD_P$77") (pintype "bidirectional"))
      (node (ref "U1") (pin "P$78") (pinfunction "VSS_PAD_P$78") (pintype "bidirectional"))
      (node (ref "U1") (pin "P$79") (pinfunction "VSS_PAD_P$79") (pintype "bidirectional"))
      (node (ref "U1") (pin "P$80") (pinfunction "VSS_PAD_P$80") (pintype "bidirectional"))
      (node (ref "U1") (pin "P$81") (pinfunction "VSS_PAD_P$81") (pintype "bidirectional"))
      (node (ref "U1") (pin "P$82") (pinfunction "VSS_PAD_P$82") (pintype "bidirectional"))
      (node (ref "U1") (pin "P$83") (pinfunction "VSS_PAD_P$83") (pintype "bidirectional"))
      (node (ref "U1") (pin "P$84") (pinfunction "VSS_PAD_P$84") (pintype "bidirectional"))
      (node (ref "U1") (pin "P$85") (pinfunction "VSS_PAD_P$85") (pintype "bidirectional"))
      (node (ref "U1") (pin "P$86") (pinfunction "VSS_PAD_P$86") (pintype "bidirectional"))
      (node (ref "U1") (pin "P$87") (pinfunction "VSS_PAD_P$87") (pintype "bidirectional"))
      (node (ref "U1") (pin "P$88") (pinfunction "VSS_PAD_P$88") (pintype "bidirectional"))
      (node (ref "U1") (pin "P$89") (pinfunction "VSS_PAD_P$89") (pintype "bidirectional"))
      (node (ref "U1") (pin "P$90") (pinfunction "VSS_PAD_P$90") (pintype "bidirectional"))
      (node (ref "U1") (pin "P$B7") (pinfunction "VSS_P$B7") (pintype "power_in"))
      (node (ref "U1") (pin "P$F23") (pinfunction "VSS_PA_P$F23") (pintype "bidirectional"))
      (node (ref "U3") (pin "1") (pinfunction "CTG_1") (pintype "power_in"))
      (node (ref "U3") (pin "4") (pinfunction "GND_4") (pintype "power_in"))
      (node (ref "U3") (pin "6") (pinfunction "QSTRT_6") (pintype "input"))
      (node (ref "U3") (pin "9") (pinfunction "EP_9") (pintype "power_in"))
      (node (ref "X1") (pin "2") (pinfunction "2_2") (pintype "passive"))
      (node (ref "X1") (pin "4") (pinfunction "4_4") (pintype "passive"))
    )
    (net (code "14") (name "HAPTIC_EN") (class "Default")
      (node (ref "IC2") (pin "A1") (pinfunction "EN_A1") (pintype "bidirectional"))
      (node (ref "U1") (pin "P$U1") (pinfunction "P0.12_P$U1") (pintype "bidirectional"))
    )
    (net (code "15") (name "IMU_INT1") (class "Default")
      (node (ref "IC3") (pin "5") (pinfunction "INT1_5") (pintype "bidirectional"))
      (node (ref "U1") (pin "P$N1") (pinfunction "P0.08_P$N1") (pintype "bidirectional"))
    )
    (net (code "16") (name "IMU_INT2") (class "Default")
      (node (ref "IC3") (pin "6") (pinfunction "INT2_6") (pintype "bidirectional"))
      (node (ref "U1") (pin "P$P2") (pinfunction "P1.08_P$P2") (pintype "bidirectional"))
    )
    (net (code "17") (name "LX1") (class "Default")
      (node (ref "IC9") (pin "B2") (pinfunction "SW1_1_B2") (pintype "bidirectional"))
      (node (ref "IC9") (pin "B3") (pinfunction "SW1_2_B3") (pintype "bidirectional"))
      (node (ref "L7") (pin "1") (pinfunction "1_1") (pintype "bidirectional"))
    )
    (net (code "18") (name "LX2") (class "Default")
      (node (ref "IC9") (pin "D2") (pinfunction "SW2_1_D2") (pintype "bidirectional"))
      (node (ref "IC9") (pin "D3") (pinfunction "SW2_2_D3") (pintype "bidirectional"))
      (node (ref "L7") (pin "2") (pinfunction "2_2") (pintype "bidirectional"))
    )
    (net (code "19") (name "MOSI") (class "Default")
      (node (ref "J1") (pin "14") (pinfunction "14_14") (pintype "bidirectional"))
      (node (ref "U1") (pin "P$B13") (pinfunction "P0.03/AIN1_P$B13") (pintype "bidirectional"))
    )
    (net (code "20") (name "Net-(ANT1-FEED)") (class "Default")
      (node (ref "ANT1") (pin "1") (pinfunction "FEED_1") (pintype "input"))
      (node (ref "C22") (pin "2") (pinfunction "2_2") (pintype "passive"))
      (node (ref "C4") (pin "2") (pinfunction "2_2") (pintype "passive"))
      (node (ref "L1") (pin "2") (pinfunction "2_2") (pintype "passive"))
    )
    (net (code "21") (name "Net-(D2-K)") (class "Default")
      (node (ref "C2-EP-DR") (pin "1") (pinfunction "1_1") (pintype "passive"))
      (node (ref "D2") (pin "1") (pinfunction "K_1") (pintype "bidirectional"))
      (node (ref "D4") (pin "2") (pinfunction "A_2") (pintype "bidirectional"))
    )
    (net (code "22") (name "Net-(D5-A)") (class "Default")
      (node (ref "C2-EP-DR") (pin "2") (pinfunction "2_2") (pintype "passive"))
      (node (ref "D5") (pin "2") (pinfunction "A_2") (pintype "bidirectional"))
      (node (ref "L5") (pin "1") (pinfunction "1_1") (pintype "passive"))
      (node (ref "Q3") (pin "3") (pinfunction "D_3") (pintype "bidirectional"))
    )
    (net (code "23") (name "Net-(EPD_C1-Pad2)") (class "Default")
      (node (ref "EPD_C1") (pin "2") (pinfunction "2_2") (pintype "passive"))
      (node (ref "J1") (pin "5") (pinfunction "5_5") (pintype "bidirectional"))
    )
    (net (code "24") (name "Net-(EPD_C2-Pad2)") (class "Default")
      (node (ref "EPD_C2") (pin "2") (pinfunction "2_2") (pintype "passive"))
      (node (ref "J1") (pin "4") (pinfunction "4_4") (pintype "bidirectional"))
    )
    (net (code "25") (name "Net-(EPD_C6-Pad2)") (class "Default")
      (node (ref "EPD_C6") (pin "2") (pinfunction "2_2") (pintype "passive"))
      (node (ref "J1") (pin "18") (pinfunction "18_18") (pintype "bidirectional"))
    )
    (net (code "26") (name "Net-(EPD_C7-Pad2)") (class "Default")
      (node (ref "EPD_C7") (pin "2") (pinfunction "2_2") (pintype "passive"))
      (node (ref "J1") (pin "19") (pinfunction "19_19") (pintype "bidirectional"))
    )
    (net (code "27") (name "Net-(EPD_C8-Pad2)") (class "Default")
      (node (ref "EPD_C8") (pin "2") (pinfunction "2_2") (pintype "passive"))
      (node (ref "J1") (pin "20") (pinfunction "20_20") (pintype "bidirectional"))
    )
    (net (code "28") (name "Net-(EPD_C10-Pad2)") (class "Default")
      (node (ref "EPD_C10") (pin "2") (pinfunction "2_2") (pintype "passive"))
      (node (ref "J1") (pin "22") (pinfunction "22_22") (pintype "bidirectional"))
    )
    (net (code "29") (name "Net-(EPD_C12-Pad2)") (class "Default")
      (node (ref "EPD_C12") (pin "2") (pinfunction "2_2") (pintype "passive"))
      (node (ref "J1") (pin "24") (pinfunction "24_24") (pintype "bidirectional"))
    )
    (net (code "30") (name "Net-(IC1-TS{slash}MR)") (class "Default")
      (node (ref "IC1") (pin "D1") (pinfunction "TS/MR_D1") (pintype "bidirectional"))
      (node (ref "R9") (pin "2") (pinfunction "2_2") (pintype "bidirectional"))
    )
    (net (code "31") (name "Net-(IC2-REG)") (class "Default")
      (node (ref "C32") (pin "2") (pinfunction "2_2") (pintype "passive"))
      (node (ref "IC2") (pin "A2") (pinfunction "REG_A2") (pintype "bidirectional"))
    )
    (net (code "32") (name "Net-(IC3-SDO)") (class "Default")
      (node (ref "IC3") (pin "1") (pinfunction "SDO_1") (pintype "bidirectional"))
      (node (ref "R3") (pin "2") (pinfunction "2_2") (pintype "bidirectional"))
    )
    (net (code "33") (name "Net-(IC9-SCL)") (class "Default")
      (node (ref "IC9") (pin "D1") (pinfunction "SCL_D1") (pintype "bidirectional"))
      (node (ref "R4") (pin "2") (pinfunction "2_2") (pintype "bidirectional"))
    )
    (net (code "34") (name "Net-(IC9-SDA)") (class "Default")
      (node (ref "IC9") (pin "E1") (pinfunction "SDA_E1") (pintype "bidirectional"))
      (node (ref "R2") (pin "2") (pinfunction "2_2") (pintype "bidirectional"))
    )
    (net (code "35") (name "Net-(J4-CC1)") (class "Default")
      (node (ref "J4") (pin "A5") (pinfunction "CC1_A5") (pintype "bidirectional"))
      (node (ref "R1_USB") (pin "2") (pinfunction "2_2") (pintype "bidirectional"))
    )
    (net (code "36") (name "Net-(J4-CC2)") (class "Default")
      (node (ref "J4") (pin "B5") (pinfunction "CC2_B5") (pintype "bidirectional"))
      (node (ref "R2_USB") (pin "1") (pinfunction "1_1") (pintype "bidirectional"))
    )
    (net (code "37") (name "Net-(L2-Pad2)") (class "Default")
      (node (ref "L2") (pin "2") (pinfunction "2_2") (pintype "passive"))
      (node (ref "L3") (pin "1") (pinfunction "1_1") (pintype "passive"))
    )
    (net (code "38") (name "Net-(R1_EP_DR-Pad1)") (class "Default")
      (node (ref "R1_EP_DR") (pin "1") (pinfunction "1_1") (pintype "bidirectional"))
      (node (ref "R_TYPE_SEL") (pin "2") (pinfunction "2_2") (pintype "bidirectional"))
      (node (ref "SJ1") (pin "2") (pinfunction "2_2") (pintype "passive"))
    )
    (net (code "39") (name "Net-(U1-ANT)") (class "Default")
      (node (ref "C3") (pin "2") (pinfunction "2_2") (pintype "passive"))
      (node (ref "L1") (pin "1") (pinfunction "1_1") (pintype "passive"))
      (node (ref "U1") (pin "P$H23") (pinfunction "ANT_P$H23") (pintype "bidirectional"))
    )
    (net (code "40") (name "Net-(U1-DCC)") (class "Default")
      (node (ref "L2") (pin "1") (pinfunction "1_1") (pintype "passive"))
      (node (ref "U1") (pin "P$B3") (pinfunction "DCC_P$B3") (pintype "output"))
    )
    (net (code "41") (name "Net-(U1-DEC1)") (class "Default")
      (node (ref "C5") (pin "1") (pinfunction "1_1") (pintype "passive"))
      (node (ref "U1") (pin "P$C1") (pinfunction "DEC1_P$C1") (pintype "power_in"))
    )
    (net (code "42") (name "Net-(U1-DEC2)") (class "Default")
      (node (ref "C13") (pin "2") (pinfunction "2_2") (pintype "passive"))
      (node (ref "U1") (pin "P$A18") (pinfunction "DEC2_P$A18") (pintype "bidirectional"))
    )
    (net (code "43") (name "Net-(U1-DEC3)") (class "Default")
      (node (ref "C11") (pin "2") (pinfunction "2_2") (pintype "passive"))
      (node (ref "U1") (pin "P$D23") (pinfunction "DEC3_P$D23") (pintype "bidirectional"))
    )
    (net (code "44") (name "Net-(U1-DEC3V3)") (class "Default")
      (node (ref "C20") (pin "1") (pinfunction "1_1") (pintype "passive"))
      (node (ref "U1") (pin "P$AC5") (pinfunction "DEC3V3_P$AC5") (pintype "bidirectional"))
    )
    (net (code "45") (name "Net-(U1-DEC4)") (class "Default")
      (node (ref "C10") (pin "2") (pinfunction "2_2") (pintype "passive"))
      (node (ref "C15") (pin "1") (pinfunction "1_1") (pintype "passive"))
      (node (ref "C16") (pin "2") (pinfunction "2_2") (pintype "passive"))
      (node (ref "L3") (pin "2") (pinfunction "2_2") (pintype "passive"))
      (node (ref "U1") (pin "P$B5") (pinfunction "DEC4_P$B5") (pintype "power_in"))
      (node (ref "U1") (pin "P$E24") (pinfunction "DEC6_P$E24") (pintype "bidirectional"))
    )
    (net (code "46") (name "Net-(U1-DEC5)") (class "Default")
      (node (ref "C9") (pin "2") (pinfunction "2_2") (pintype "passive"))
      (node (ref "U1") (pin "P$N24") (pinfunction "DEC5_P$N24") (pintype "bidirectional"))
    )
    (net (code "47") (name "Net-(U1-P0.00{slash}XL1)") (class "Default")
      (node (ref "C17") (pin "2") (pinfunction "2_2") (pintype "passive"))
      (node (ref "U1") (pin "P$D2") (pinfunction "P0.00/XL1_P$D2") (pintype "bidirectional"))
      (node (ref "X2\\") (pin "1") (pinfunction "1_1") (pintype "passive"))
    )
    (net (code "48") (name "Net-(U1-P0.01{slash}XL2)") (class "Default")
      (node (ref "C18") (pin "2") (pinfunction "2_2") (pintype "passive"))
      (node (ref "U1") (pin "P$F2") (pinfunction "P0.01/XL2_P$F2") (pintype "bidirectional"))
      (node (ref "X2\\") (pin "2") (pinfunction "2_2") (pintype "passive"))
    )
    (net (code "49") (name "Net-(U1-XC1)") (class "Default")
      (node (ref "C1") (pin "1") (pinfunction "1_1") (pintype "passive"))
      (node (ref "C2") (pin "1") (pinfunction "1_1") (pintype "passive"))
      (node (ref "U1") (pin "P$B24") (pinfunction "XC1_P$B24") (pintype "input"))
      (node (ref "X1") (pin "1") (pinfunction "1_1") (pintype "passive"))
      (node (ref "X1") (pin "3") (pinfunction "3_3") (pintype "passive"))
    )
    (net (code "50") (name "OUT+") (class "Default")
      (node (ref "IC2") (pin "A3") (pinfunction "OUT+_A3") (pintype "bidirectional"))
      (node (ref "TP_OP") (pin "TP") (pinfunction "TP_TP") (pintype "input"))
    )
    (net (code "51") (name "OUT-") (class "Default")
      (node (ref "IC2") (pin "C3") (pinfunction "OUT-_C3") (pintype "bidirectional"))
      (node (ref "TP_ON") (pin "TP") (pinfunction "TP_TP") (pintype "input"))
    )
    (net (code "52") (name "P0.04") (class "Default")
      (node (ref "U1") (pin "P$J1") (pinfunction "P0.04/AIN2_P$J1") (pintype "bidirectional"))
    )
    (net (code "53") (name "P0.13") (class "Default")
      (node (ref "C30") (pin "2") (pinfunction "2_2") (pintype "passive"))
      (node (ref "R5") (pin "1") (pinfunction "1_1") (pintype "bidirectional"))
      (node (ref "SW_UP") (pin "2") (pinfunction "2_2") (pintype "passive"))
      (node (ref "U1") (pin "P$AD8") (pinfunction "P0.13_P$AD8") (pintype "bidirectional"))
    )
    (net (code "54") (name "P0.14") (class "Default")
      (node (ref "C31") (pin "2") (pinfunction "2_2") (pintype "passive"))
      (node (ref "R8") (pin "1") (pinfunction "1_1") (pintype "bidirectional"))
      (node (ref "SW_ENT") (pin "2") (pinfunction "2_2") (pintype "passive"))
      (node (ref "U1") (pin "P$AC9") (pinfunction "P0.14_P$AC9") (pintype "bidirectional"))
    )
    (net (code "55") (name "P0.19") (class "Default")
      (node (ref "U1") (pin "P$AC15") (pinfunction "P0.19_P$AC15") (pintype "bidirectional"))
    )
    (net (code "56") (name "P0.20") (class "Default")
      (node (ref "U1") (pin "P$AD16") (pinfunction "P0.20_P$AD16") (pintype "bidirectional"))
    )
    (net (code "57") (name "P0.21") (class "Default")
      (node (ref "U1") (pin "P$AC17") (pinfunction "P0.21_P$AC17") (pintype "bidirectional"))
    )
    (net (code "58") (name "P0.22") (class "Default")
      (node (ref "U1") (pin "P$AD18") (pinfunction "P0.22_P$AD18") (pintype "bidirectional"))
    )
    (net (code "59") (name "P0.23") (class "Default")
      (node (ref "U1") (pin "P$AC19") (pinfunction "P0.23_P$AC19") (pintype "bidirectional"))
    )
    (net (code "60") (name "P0.24") (class "Default")
      (node (ref "U1") (pin "P$AD20") (pinfunction "P0.24_P$AD20") (pintype "bidirectional"))
    )
    (net (code "61") (name "P0.25") (class "Default")
      (node (ref "U1") (pin "P$AC21") (pinfunction "P0.25_P$AC21") (pintype "bidirectional"))
    )
    (net (code "62") (name "P0.26") (class "Default")
      (node (ref "U1") (pin "P$G1") (pinfunction "P0.26_P$G1") (pintype "bidirectional"))
    )
    (net (code "63") (name "P0.27") (class "Default")
      (node (ref "U1") (pin "P$H2") (pinfunction "P0.27_P$H2") (pintype "bidirectional"))
    )
    (net (code "64") (name "P0.28") (class "Default")
      (node (ref "U1") (pin "P$B11") (pinfunction "P0.28/AIN4_P$B11") (pintype "bidirectional"))
    )
    (net (code "65") (name "P0.29") (class "Default")
      (node (ref "U1") (pin "P$A10") (pinfunction "P0.29/AIN5_P$A10") (pintype "bidirectional"))
    )
    (net (code "66") (name "P0.30") (class "Default")
      (node (ref "U1") (pin "P$B9") (pinfunction "P0.30/AIN6_P$B9") (pintype "bidirectional"))
    )
    (net (code "67") (name "P0.31") (class "Default")
      (node (ref "U1") (pin "P$A8") (pinfunction "P0.31/AIN7_P$A8") (pintype "bidirectional"))
    )
    (net (code "68") (name "P1.01") (class "Default")
      (node (ref "Q1") (pin "1") (pinfunction "G_1") (pintype "bidirectional"))
      (node (ref "R_PWR_EPD") (pin "1") (pinfunction "1_1") (pintype "bidirectional"))
      (node (ref "U1") (pin "P$Y23") (pinfunction "P1.01_P$Y23") (pintype "bidirectional"))
    )
    (net (code "69") (name "P1.02") (class "Default")
      (node (ref "C29") (pin "1") (pinfunction "1_1") (pintype "passive"))
      (node (ref "R7") (pin "1") (pinfunction "1_1") (pintype "bidirectional"))
      (node (ref "SW_DN") (pin "2") (pinfunction "2_2") (pintype "passive"))
      (node (ref "U1") (pin "P$W24") (pinfunction "P1.02_P$W24") (pintype "bidirectional"))
    )
    (net (code "70") (name "P1.03") (class "Default")
      (node (ref "U1") (pin "P$V23") (pinfunction "P1.03_P$V23") (pintype "bidirectional"))
    )
    (net (code "71") (name "P1.04") (class "Default")
      (node (ref "U1") (pin "P$U24") (pinfunction "P1.04_P$U24") (pintype "bidirectional"))
    )
    (net (code "72") (name "P1.05") (class "Default")
      (node (ref "U1") (pin "P$T23") (pinfunction "P1.05_P$T23") (pintype "bidirectional"))
    )
    (net (code "73") (name "P1.06") (class "Default")
      (node (ref "U1") (pin "P$R24") (pinfunction "P1.06_P$R24") (pintype "bidirectional"))
    )
    (net (code "74") (name "P1.07") (class "Default")
      (node (ref "U1") (pin "P$P23") (pinfunction "P1.07_P$P23") (pintype "bidirectional"))
    )
    (net (code "75") (name "P1.09") (class "Default")
      (node (ref "U1") (pin "P$L24") (pinfunction "P0.09/NFC1_P$L24") (pintype "bidirectional"))
      (node (ref "U1") (pin "P$R1") (pinfunction "P1.09_P$R1") (pintype "bidirectional"))
    )
    (net (code "76") (name "P1.10") (class "Default")
      (node (ref "U1") (pin "P$A20") (pinfunction "P1.10_P$A20") (pintype "bidirectional"))
    )
    (net (code "77") (name "P1.11") (class "Default")
      (node (ref "U1") (pin "P$B19") (pinfunction "P1.11_P$B19") (pintype "bidirectional"))
    )
    (net (code "78") (name "P1.12") (class "Default")
      (node (ref "U1") (pin "P$B17") (pinfunction "P1.12_P$B17") (pintype "bidirectional"))
    )
    (net (code "79") (name "P1.13") (class "Default")
      (node (ref "U1") (pin "P$A16") (pinfunction "P1.13_P$A16") (pintype "bidirectional"))
    )
    (net (code "80") (name "P1.14") (class "Default")
      (node (ref "U1") (pin "P$B15") (pinfunction "P1.14_P$B15") (pintype "bidirectional"))
    )
    (net (code "81") (name "P1.15") (class "Default")
      (node (ref "U1") (pin "P$A14") (pinfunction "P1.15_P$A14") (pintype "bidirectional"))
    )
    (net (code "82") (name "PMIC_INT") (class "Default")
      (node (ref "IC1") (pin "A1") (pinfunction "~{INT}_A1") (pintype "bidirectional"))
      (node (ref "U1") (pin "P$T2") (pinfunction "P0.11_P$T2") (pintype "bidirectional"))
    )
    (net (code "83") (name "PREVGH") (class "Default")
      (node (ref "D5") (pin "1") (pinfunction "K_1") (pintype "bidirectional"))
      (node (ref "EPD_C9") (pin "2") (pinfunction "2_2") (pintype "passive"))
      (node (ref "J1") (pin "21") (pinfunction "21_21") (pintype "bidirectional"))
    )
    (net (code "84") (name "PREVGL") (class "Default")
      (node (ref "D2") (pin "2") (pinfunction "A_2") (pintype "bidirectional"))
      (node (ref "EPD_C11") (pin "2") (pinfunction "2_2") (pintype "passive"))
      (node (ref "J1") (pin "23") (pinfunction "23_23") (pintype "bidirectional"))
    )
    (net (code "85") (name "RESE") (class "Default")
      (node (ref "J1") (pin "3") (pinfunction "3_3") (pintype "bidirectional"))
      (node (ref "Q3") (pin "2") (pinfunction "S_2") (pintype "bidirectional"))
      (node (ref "R1_EP_DR") (pin "2") (pinfunction "2_2") (pintype "bidirectional"))
    )
    (net (code "86") (name "RESET") (class "Default")
      (node (ref "J2") (pin "6") (pinfunction "6_6") (pintype "bidirectional"))
      (node (ref "TP_RESET1") (pin "TP") (pinfunction "TP_TP") (pintype "input"))
      (node (ref "U1") (pin "P$AC13") (pinfunction "P0.18/RESET_P$AC13") (pintype "bidirectional"))
    )
    (net (code "87") (name "SCK") (class "Default")
      (node (ref "J1") (pin "13") (pinfunction "13_13") (pintype "bidirectional"))
      (node (ref "U1") (pin "P$A12") (pinfunction "P0.02/AIN0_P$A12") (pintype "bidirectional"))
    )
    (net (code "88") (name "SCL") (class "Default")
      (node (ref "IC1") (pin "B1") (pinfunction "SCL_B1") (pintype "bidirectional"))
      (node (ref "IC2") (pin "C1") (pinfunction "SCL_C1") (pintype "bidirectional"))
      (node (ref "IC3") (pin "12") (pinfunction "SCX_12") (pintype "bidirectional"))
      (node (ref "R17") (pin "2") (pinfunction "2_2") (pintype "bidirectional"))
      (node (ref "R4") (pin "1") (pinfunction "1_1") (pintype "bidirectional"))
      (node (ref "TP_SCL1") (pin "TP") (pinfunction "TP_TP") (pintype "input"))
      (node (ref "U1") (pin "P$M2") (pinfunction "P0.07_P$M2") (pintype "bidirectional"))
      (node (ref "U3") (pin "7") (pinfunction "SCL_7") (pintype "input"))
    )
    (net (code "89") (name "SDA") (class "Default")
      (node (ref "IC1") (pin "C1") (pinfunction "SDA_C1") (pintype "bidirectional"))
      (node (ref "IC2") (pin "B2") (pinfunction "SDA_B2") (pintype "bidirectional"))
      (node (ref "IC3") (pin "2") (pinfunction "SDX_2") (pintype "bidirectional"))
      (node (ref "R18") (pin "2") (pinfunction "2_2") (pintype "bidirectional"))
      (node (ref "R2") (pin "1") (pinfunction "1_1") (pintype "bidirectional"))
      (node (ref "TP_SDA1") (pin "TP") (pinfunction "TP_TP") (pintype "input"))
      (node (ref "U1") (pin "P$L1") (pinfunction "P0.06_P$L1") (pintype "bidirectional"))
      (node (ref "U3") (pin "8") (pinfunction "SDA_8") (pintype "bidirectional"))
    )
    (net (code "90") (name "SWDCLK") (class "Default")
      (node (ref "J2") (pin "4") (pinfunction "4_4") (pintype "bidirectional"))
      (node (ref "TP_SWDCLK1") (pin "TP") (pinfunction "TP_TP") (pintype "input"))
      (node (ref "U1") (pin "P$AA24") (pinfunction "SWDCLK_P$AA24") (pintype "input"))
    )
    (net (code "91") (name "SWDIO") (class "Default")
      (node (ref "J2") (pin "2") (pinfunction "2_2") (pintype "bidirectional"))
      (node (ref "TP_SWDIO1") (pin "TP") (pinfunction "TP_TP") (pintype "input"))
      (node (ref "U1") (pin "P$AC24") (pinfunction "SWDIO_P$AC24") (pintype "bidirectional"))
    )
    (net (code "92") (name "SWO") (class "Default")
      (node (ref "TP_SWO1") (pin "TP") (pinfunction "TP_TP") (pintype "input"))
      (node (ref "U1") (pin "P$AD22") (pinfunction "P1.00_P$AD22") (pintype "bidirectional"))
    )
    (net (code "93") (name "VBAT") (class "Default")
      (node (ref "C27") (pin "2") (pinfunction "2_2") (pintype "passive"))
      (node (ref "C37") (pin "1") (pinfunction "1_1") (pintype "passive"))
      (node (ref "IC1") (pin "C2") (pinfunction "BAT_C2") (pintype "bidirectional"))
      (node (ref "TP_VBAT") (pin "TP") (pinfunction "TP_TP") (pintype "input"))
      (node (ref "U3") (pin "2") (pinfunction "CELL_2") (pintype "power_in"))
      (node (ref "U3") (pin "3") (pinfunction "VDD_3") (pintype "power_in"))
    )
    (net (code "94") (name "VBUS") (class "Default")
      (node (ref "C21") (pin "1") (pinfunction "1_1") (pintype "passive"))
      (node (ref "C38") (pin "1") (pinfunction "1_1") (pintype "passive"))
      (node (ref "C42") (pin "1") (pinfunction "1_1") (pintype "passive"))
      (node (ref "C43") (pin "1") (pinfunction "1_1") (pintype "passive"))
      (node (ref "D3") (pin "5") (pinfunction "VBUS_5") (pintype "bidirectional"))
      (node (ref "IC1") (pin "A2") (pinfunction "IN_A2") (pintype "bidirectional"))
      (node (ref "J4") (pin "A4_B9") (pinfunction "VBUS_A4_B9") (pintype "power_in"))
      (node (ref "J4") (pin "A9_B4") (pinfunction "VBUS_A9_B4") (pintype "power_in"))
      (node (ref "U1") (pin "P$AD2") (pinfunction "VBUS_P$AD2") (pintype "power_in"))
    )
    (net (code "95") (name "VREG") (class "Default")
      (node (ref "C23") (pin "2") (pinfunction "2_2") (pintype "passive"))
      (node (ref "C24") (pin "2") (pinfunction "2_2") (pintype "passive"))
      (node (ref "C39") (pin "1") (pinfunction "1_1") (pintype "passive"))
      (node (ref "IC1") (pin "B2") (pinfunction "SYS_B2") (pintype "bidirectional"))
      (node (ref "IC9") (pin "A1") (pinfunction "EN_A1") (pintype "bidirectional"))
      (node (ref "IC9") (pin "A2") (pinfunction "VIN_1_A2") (pintype "bidirectional"))
      (node (ref "IC9") (pin "A3") (pinfunction "VIN_2_A3") (pintype "bidirectional"))
      (node (ref "TP_VREG") (pin "TP") (pinfunction "TP_TP") (pintype "input"))
    )
    (net (code "96") (name "unconnected-(ANT1-NC-Pad2)") (class "Default")
      (node (ref "ANT1") (pin "2") (pinfunction "NC_2") (pintype "no_connect"))
    )
    (net (code "97") (name "unconnected-(IC3-ASCL-Pad11)") (class "Default")
      (node (ref "IC3") (pin "11") (pinfunction "ASCL_11") (pintype "bidirectional"))
    )
    (net (code "98") (name "unconnected-(IC3-ASDA-Pad4)") (class "Default")
      (node (ref "IC3") (pin "4") (pinfunction "ASDA_4") (pintype "bidirectional"))
    )
    (net (code "99") (name "unconnected-(J1-Pad1)") (class "Default")
      (node (ref "J1") (pin "1") (pinfunction "1_1") (pintype "bidirectional"))
    )
    (net (code "100") (name "unconnected-(J1-Pad6)") (class "Default")
      (node (ref "J1") (pin "6") (pinfunction "6_6") (pintype "bidirectional"))
    )
    (net (code "101") (name "unconnected-(J1-Pad7)") (class "Default")
      (node (ref "J1") (pin "7") (pinfunction "7_7") (pintype "bidirectional"))
    )
    (net (code "102") (name "unconnected-(J4-SBU1-PadA8)") (class "Default")
      (node (ref "J4") (pin "A8") (pinfunction "SBU1_A8") (pintype "bidirectional"))
    )
    (net (code "103") (name "unconnected-(J4-SBU2-PadB8)") (class "Default")
      (node (ref "J4") (pin "B8") (pinfunction "SBU2_B8") (pintype "bidirectional"))
    )
    (net (code "104") (name "unconnected-(U1-DCCH-PadP$AB2)") (class "Default")
      (node (ref "U1") (pin "P$AB2") (pinfunction "DCCH_P$AB2") (pintype "bidirectional"))
    )
    (net (code "105") (name "unconnected-(U1-XC2-PadP$A23)") (class "Default")
      (node (ref "U1") (pin "P$A23") (pinfunction "XC2_P$A23") (pintype "output"))
    )
  )
)
